# GridEYE-Breakout.net
KiCad netlist of a schematic drawn in EAGLE
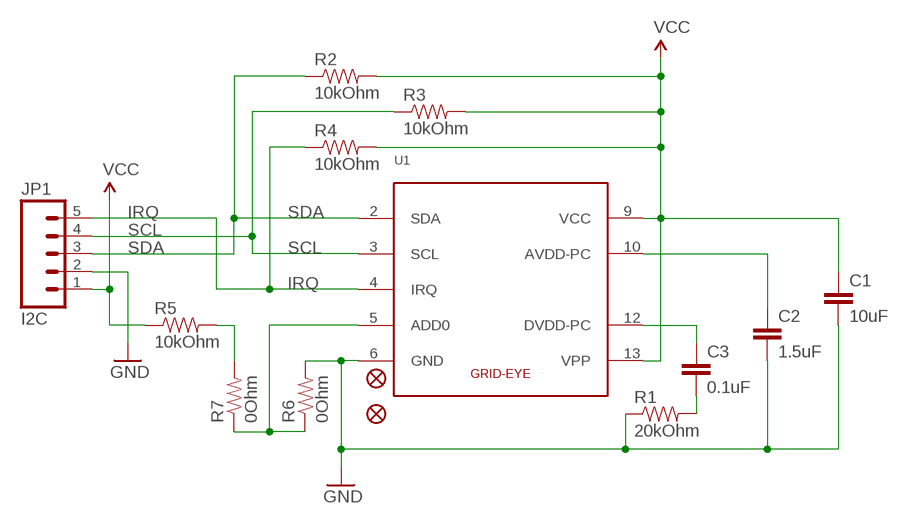
[diagram p0: schematic, sheet 1]

(export (version "E")
  (design (tool "Eeschema 10.0.6"))
  (components
    (comp (ref "C1")
      (value "10uF")
      (footprint "eagle-import:0603-CAP")
      (libsource (lib "eagle-import") (part "CAP0603-CAP"))
    )
    (comp (ref "C2")
      (value "1.5uF")
      (footprint "eagle-import:0603-CAP")
      (libsource (lib "eagle-import") (part "CAP0603-CAP"))
    )
    (comp (ref "C3")
      (value "0.1uF")
      (footprint "eagle-import:0603-CAP")
      (libsource (lib "eagle-import") (part "CAP0603-CAP"))
    )
    (comp (ref "JP1")
      (value "I2C")
      (footprint "eagle-import:1X05")
      (libsource (lib "eagle-import") (part "M05PTH"))
    )
    (comp (ref "JP2")
      (value "FIDUCIAL1X2")
      (footprint "eagle-import:FIDUCIAL-1X2")
      (libsource (lib "eagle-import") (part "FIDUCIAL1X2"))
    )
    (comp (ref "JP3")
      (value "FIDUCIAL1X2")
      (footprint "eagle-import:FIDUCIAL-1X2")
      (libsource (lib "eagle-import") (part "FIDUCIAL1X2"))
    )
    (comp (ref "R1")
      (value "20kOhm")
      (footprint "eagle-import:0603-RES")
      (libsource (lib "eagle-import") (part "RESISTOR0603-RES"))
    )
    (comp (ref "R2")
      (value "10kOhm")
      (footprint "eagle-import:0603-RES")
      (libsource (lib "eagle-import") (part "RESISTOR0603-RES"))
    )
    (comp (ref "R3")
      (value "10kOhm")
      (footprint "eagle-import:0603-RES")
      (libsource (lib "eagle-import") (part "RESISTOR0603-RES"))
    )
    (comp (ref "R4")
      (value "10kOhm")
      (footprint "eagle-import:0603-RES")
      (libsource (lib "eagle-import") (part "RESISTOR0603-RES"))
    )
    (comp (ref "R5")
      (value "10kOhm")
      (footprint "eagle-import:0603-RES")
      (libsource (lib "eagle-import") (part "RESISTOR0603-RES"))
    )
    (comp (ref "R6")
      (value "0Ohm")
      (footprint "eagle-import:0402-RES")
      (libsource (lib "eagle-import") (part "RESISTOR0402-RES"))
    )
    (comp (ref "R7")
      (value "0Ohm")
      (footprint "eagle-import:0402-RES")
      (libsource (lib "eagle-import") (part "RESISTOR0402-RES"))
    )
    (comp (ref "U1")
      (value "GRID-EYE")
      (footprint "eagle-import:GRID-EYE")
      (libsource (lib "eagle-import") (part "GRID-EYE"))
    )
  )
  (nets
    (net (code "1") (name "/IRQ") (class "Default")
      (node (ref "JP1") (pin "5") (pinfunction "5_5") (pintype "passive"))
      (node (ref "R4") (pin "1") (pinfunction "1_1") (pintype "passive"))
      (node (ref "U1") (pin "4") (pinfunction "IRQ_4") (pintype "bidirectional"))
    )
    (net (code "2") (name "/SCL") (class "Default")
      (node (ref "JP1") (pin "4") (pinfunction "4_4") (pintype "passive"))
      (node (ref "R3") (pin "1") (pinfunction "1_1") (pintype "passive"))
      (node (ref "U1") (pin "3") (pinfunction "SCL_3") (pintype "bidirectional"))
    )
    (net (code "3") (name "/SDA") (class "Default")
      (node (ref "JP1") (pin "3") (pinfunction "3_3") (pintype "passive"))
      (node (ref "R2") (pin "1") (pinfunction "1_1") (pintype "passive"))
      (node (ref "U1") (pin "2") (pinfunction "SDA_2") (pintype "bidirectional"))
    )
    (net (code "4") (name "GND") (class "Default")
      (node (ref "C1") (pin "2") (pinfunction "2_2") (pintype "passive"))
      (node (ref "C2") (pin "2") (pinfunction "2_2") (pintype "passive"))
      (node (ref "JP1") (pin "2") (pinfunction "2_2") (pintype "passive"))
      (node (ref "R1") (pin "1") (pinfunction "1_1") (pintype "passive"))
      (node (ref "R6") (pin "2") (pinfunction "2_2") (pintype "passive"))
      (node (ref "U1") (pin "6") (pinfunction "GND_6") (pintype "bidirectional"))
    )
    (net (code "5") (name "Net-(C3-Pad2)") (class "Default")
      (node (ref "C3") (pin "2") (pinfunction "2_2") (pintype "passive"))
      (node (ref "R1") (pin "2") (pinfunction "2_2") (pintype "passive"))
    )
    (net (code "6") (name "Net-(R5-Pad2)") (class "Default")
      (node (ref "R5") (pin "2") (pinfunction "2_2") (pintype "passive"))
      (node (ref "R7") (pin "2") (pinfunction "2_2") (pintype "passive"))
    )
    (net (code "7") (name "Net-(U1-ADD0)") (class "Default")
      (node (ref "R6") (pin "1") (pinfunction "1_1") (pintype "passive"))
      (node (ref "R7") (pin "1") (pinfunction "1_1") (pintype "passive"))
      (node (ref "U1") (pin "5") (pinfunction "ADD0_5") (pintype "bidirectional"))
    )
    (net (code "8") (name "Net-(U1-AVDD-PC)") (class "Default")
      (node (ref "C2") (pin "1") (pinfunction "1_1") (pintype "passive"))
      (node (ref "U1") (pin "10") (pinfunction "AVDD-PC_10") (pintype "bidirectional"))
    )
    (net (code "9") (name "Net-(U1-DVDD-PC)") (class "Default")
      (node (ref "C3") (pin "1") (pinfunction "1_1") (pintype "passive"))
      (node (ref "U1") (pin "12") (pinfunction "DVDD-PC_12") (pintype "bidirectional"))
    )
    (net (code "10") (name "VCC") (class "Default")
      (node (ref "C1") (pin "1") (pinfunction "1_1") (pintype "passive"))
      (node (ref "JP1") (pin "1") (pinfunction "1_1") (pintype "passive"))
      (node (ref "R2") (pin "2") (pinfunction "2_2") (pintype "passive"))
      (node (ref "R3") (pin "2") (pinfunction "2_2") (pintype "passive"))
      (node (ref "R4") (pin "2") (pinfunction "2_2") (pintype "passive"))
      (node (ref "R5") (pin "1") (pinfunction "1_1") (pintype "passive"))
      (node (ref "U1") (pin "13") (pinfunction "VPP_13") (pintype "bidirectional"))
      (node (ref "U1") (pin "9") (pinfunction "VCC_9") (pintype "bidirectional"))
    )
  )
)
